# Etch_a_Sketch_Front.net
KiCad netlist of a schematic drawn in EAGLE
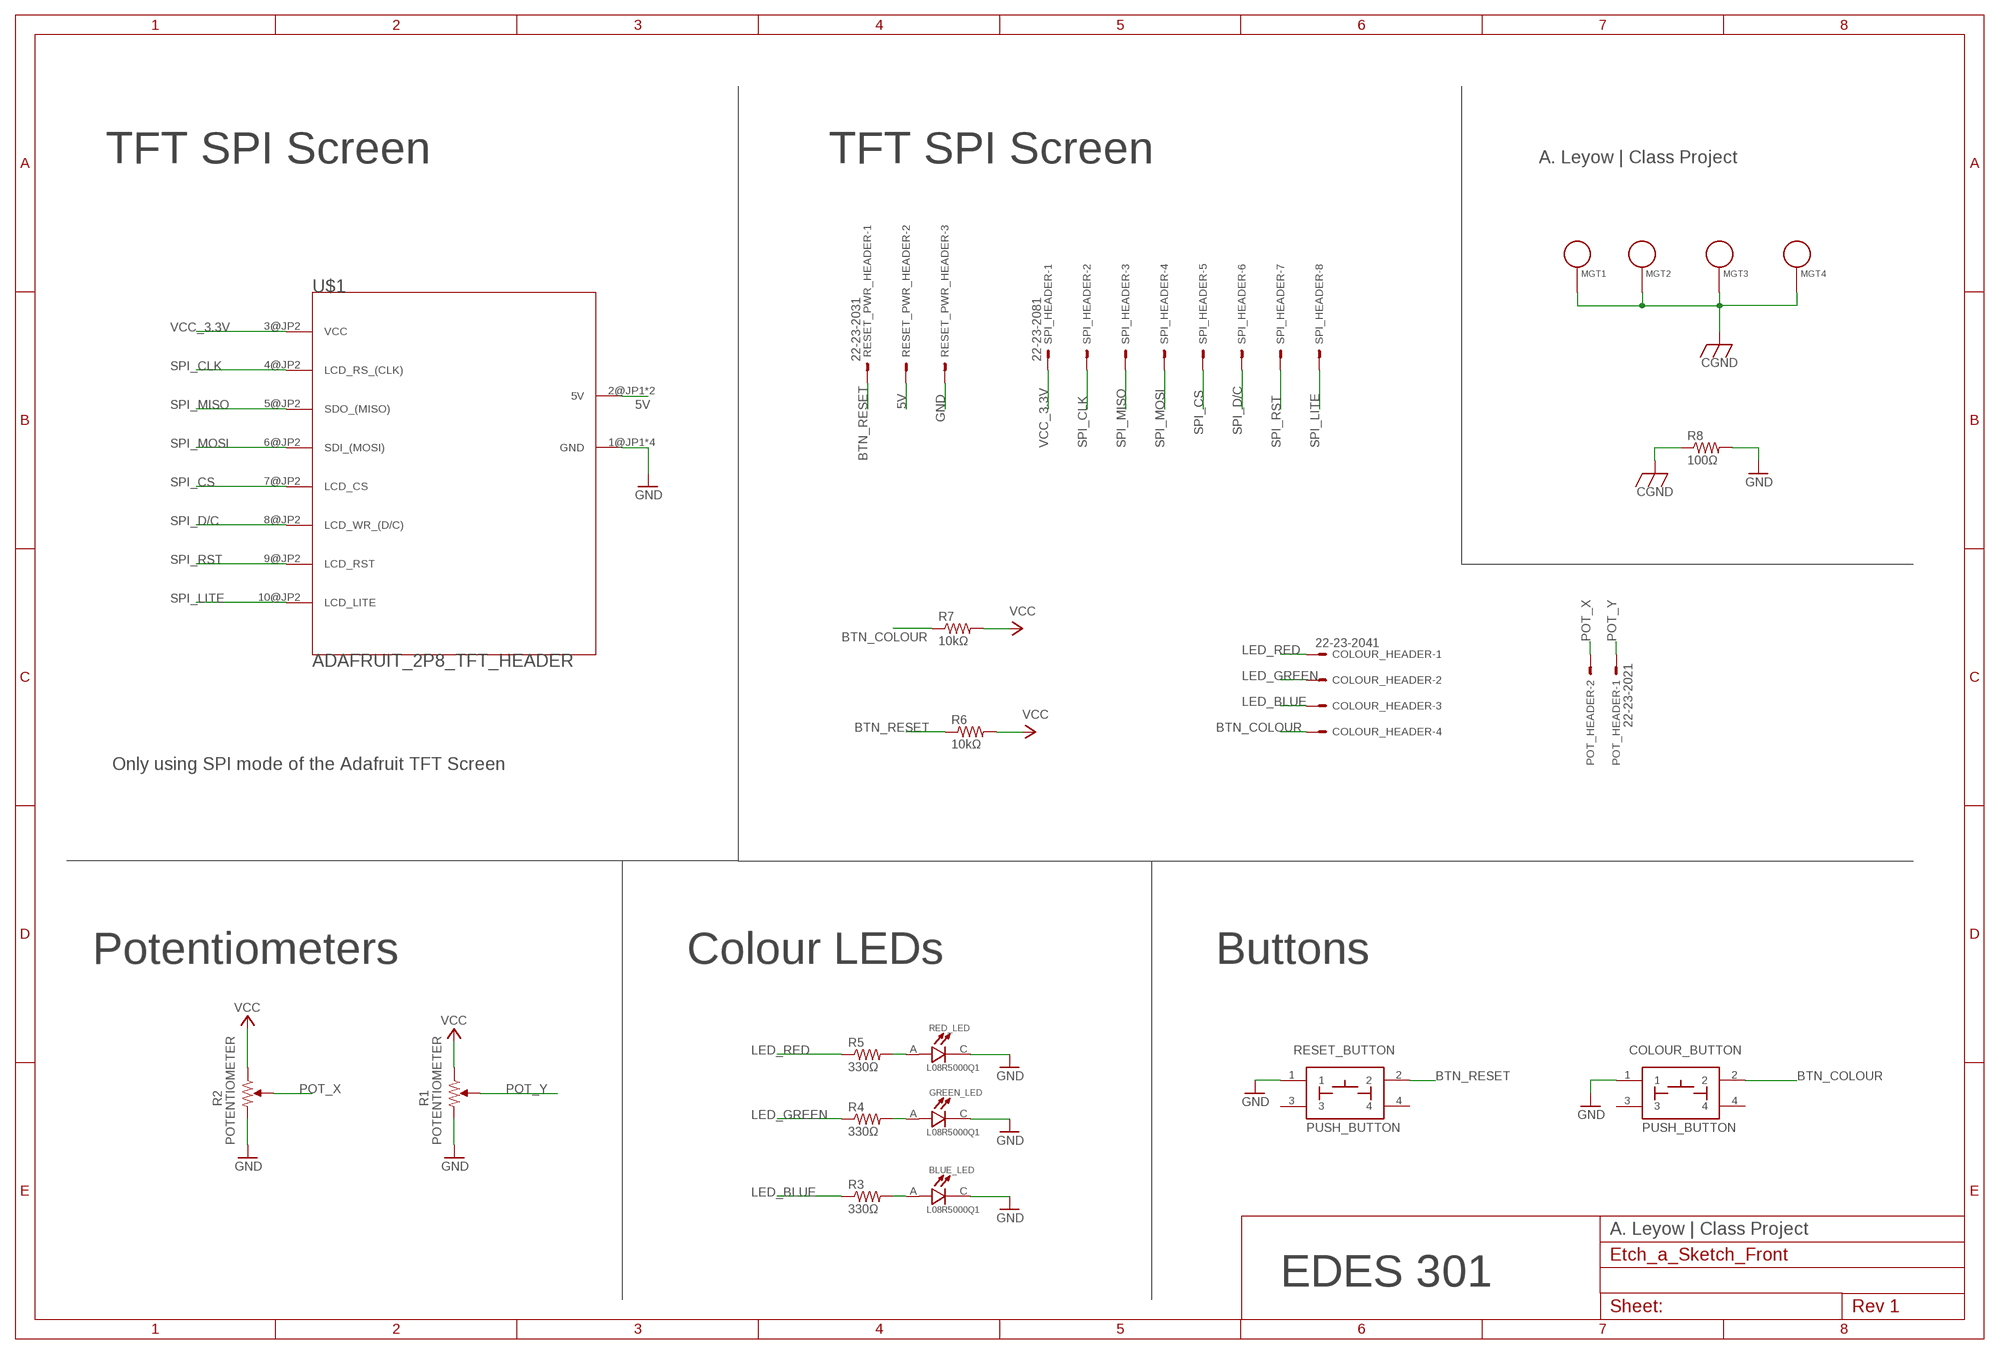
[diagram p0: schematic, sheet 1]

(export (version "E")
  (design (tool "Eeschema 10.0.6"))
  (components
    (comp (ref "BLUE_LED")
      (value "L08R5000Q1")
      (footprint "eagle-import:LEDRD254W57D500H1070")
      (fields (field (name "MF") "LED Technology"))
      (libsource (lib "eagle-import") (part "L08R5000Q1"))
    )
    (comp (ref "COLOUR_BUTTON")
      (value "PUSH_BUTTON")
      (footprint "eagle-import:BUTTON_12.5MM")
      (libsource (lib "eagle-import") (part "PUSH_BUTTON"))
    )
    (comp (ref "COLOUR_HEADER")
      (value "22-23-2041")
      (footprint "eagle-import:22-23-2041")
      (fields (field (name "MF") "MOLEX"))
      (libsource (lib "eagle-import") (part "22-23-2041"))
    )
    (comp (ref "GREEN_LED")
      (value "L08R5000Q1")
      (footprint "eagle-import:LEDRD254W57D500H1070")
      (fields (field (name "MF") "LED Technology"))
      (libsource (lib "eagle-import") (part "L08R5000Q1"))
    )
    (comp (ref "MGT1")
      (value "MOUNTING_HOLE")
      (footprint "eagle-import:MOUNTING_HOLE")
      (libsource (lib "eagle-import") (part "MOUNTING_HOLE"))
    )
    (comp (ref "MGT2")
      (value "MOUNTING_HOLE")
      (footprint "eagle-import:MOUNTING_HOLE")
      (libsource (lib "eagle-import") (part "MOUNTING_HOLE"))
    )
    (comp (ref "MGT3")
      (value "MOUNTING_HOLE")
      (footprint "eagle-import:MOUNTING_HOLE")
      (libsource (lib "eagle-import") (part "MOUNTING_HOLE"))
    )
    (comp (ref "MGT4")
      (value "MOUNTING_HOLE")
      (footprint "eagle-import:MOUNTING_HOLE")
      (libsource (lib "eagle-import") (part "MOUNTING_HOLE"))
    )
    (comp (ref "POT_HEADER")
      (value "22-23-2021")
      (footprint "eagle-import:22-23-2021")
      (fields (field (name "MF") "MOLEX"))
      (libsource (lib "eagle-import") (part "22-23-2021"))
    )
    (comp (ref "R1")
      (value "POTENTIOMETER")
      (footprint "eagle-import:POT-PO90S")
      (libsource (lib "eagle-import") (part "POTENTIOMETER"))
    )
    (comp (ref "R2")
      (value "POTENTIOMETER")
      (footprint "eagle-import:POT-PO90S")
      (libsource (lib "eagle-import") (part "POTENTIOMETER"))
    )
    (comp (ref "R3")
      (value "330Ω")
      (footprint "eagle-import:R0805")
      (libsource (lib "eagle-import") (part "R-US_R0805"))
    )
    (comp (ref "R4")
      (value "330Ω")
      (footprint "eagle-import:R0805")
      (libsource (lib "eagle-import") (part "R-US_R0805"))
    )
    (comp (ref "R5")
      (value "330Ω")
      (footprint "eagle-import:R0805")
      (libsource (lib "eagle-import") (part "R-US_R0805"))
    )
    (comp (ref "R6")
      (value "10kΩ")
      (footprint "eagle-import:R0805")
      (libsource (lib "eagle-import") (part "R-US_R0805"))
    )
    (comp (ref "R7")
      (value "10kΩ")
      (footprint "eagle-import:R0805")
      (libsource (lib "eagle-import") (part "R-US_R0805"))
    )
    (comp (ref "R8")
      (value "100Ω")
      (footprint "eagle-import:R0805")
      (libsource (lib "eagle-import") (part "R-US_R0805"))
    )
    (comp (ref "RED_LED")
      (value "L08R5000Q1")
      (footprint "eagle-import:LEDRD254W57D500H1070")
      (fields (field (name "MF") "LED Technology"))
      (libsource (lib "eagle-import") (part "L08R5000Q1"))
    )
    (comp (ref "RESET_BUTTON")
      (value "PUSH_BUTTON")
      (footprint "eagle-import:BUTTON_12.5MM")
      (libsource (lib "eagle-import") (part "PUSH_BUTTON"))
    )
    (comp (ref "RESET_PWR_HEADER")
      (value "22-23-2031")
      (footprint "eagle-import:22-23-2031")
      (fields (field (name "MF") "MOLEX"))
      (libsource (lib "eagle-import") (part "22-23-2031"))
    )
    (comp (ref "SPI_HEADER")
      (value "22-23-2081")
      (footprint "eagle-import:22-23-2081")
      (fields (field (name "MF") "MOLEX"))
      (libsource (lib "eagle-import") (part "22-23-2081"))
    )
    (comp (ref "U$1")
      (value "ADAFRUIT_2P8_TFT_HEADER")
      (footprint "eagle-import:ADAFRUIT_2P8_TFT_HEADER")
      (libsource (lib "eagle-import") (part "ADAFRUIT_2P8_TFT_HEADER"))
    )
  )
  (nets
    (net (code "1") (name "/5V") (class "Default")
      (node (ref "RESET_PWR_HEADER") (pin "2") (pinfunction "S_2") (pintype "passive"))
      (node (ref "U$1") (pin "2@JP1") (pinfunction "5V_2@JP1") (pintype "power_in"))
      (node (ref "U$1") (pin "2@JP2") (pinfunction "5V_2@JP2") (pintype "power_in"))
    )
    (net (code "2") (name "/BTN_COLOUR") (class "Default")
      (node (ref "COLOUR_BUTTON") (pin "2") (pinfunction "2_2") (pintype "bidirectional"))
      (node (ref "COLOUR_HEADER") (pin "4") (pinfunction "S_4") (pintype "passive"))
      (node (ref "R7") (pin "1") (pinfunction "1_1") (pintype "passive"))
    )
    (net (code "3") (name "/BTN_RESET") (class "Default")
      (node (ref "R6") (pin "1") (pinfunction "1_1") (pintype "passive"))
      (node (ref "RESET_BUTTON") (pin "2") (pinfunction "2_2") (pintype "bidirectional"))
      (node (ref "RESET_PWR_HEADER") (pin "1") (pinfunction "S_1") (pintype "passive"))
    )
    (net (code "4") (name "/LED_BLUE") (class "Default")
      (node (ref "COLOUR_HEADER") (pin "3") (pinfunction "S_3") (pintype "passive"))
      (node (ref "R3") (pin "1") (pinfunction "1_1") (pintype "passive"))
    )
    (net (code "5") (name "/LED_GREEN") (class "Default")
      (node (ref "COLOUR_HEADER") (pin "2") (pinfunction "S_2") (pintype "passive"))
      (node (ref "R4") (pin "1") (pinfunction "1_1") (pintype "passive"))
    )
    (net (code "6") (name "/LED_RED") (class "Default")
      (node (ref "COLOUR_HEADER") (pin "1") (pinfunction "S_1") (pintype "passive"))
      (node (ref "R5") (pin "1") (pinfunction "1_1") (pintype "passive"))
    )
    (net (code "7") (name "/POT_X") (class "Default")
      (node (ref "POT_HEADER") (pin "2") (pinfunction "S_2") (pintype "passive"))
      (node (ref "R2") (pin "S") (pinfunction "S_S") (pintype "bidirectional"))
    )
    (net (code "8") (name "/POT_Y") (class "Default")
      (node (ref "POT_HEADER") (pin "1") (pinfunction "S_1") (pintype "passive"))
      (node (ref "R1") (pin "S") (pinfunction "S_S") (pintype "bidirectional"))
    )
    (net (code "9") (name "/SPI_CLK") (class "Default")
      (node (ref "SPI_HEADER") (pin "2") (pinfunction "S_2") (pintype "passive"))
      (node (ref "U$1") (pin "4@JP2") (pinfunction "LCD_RS_(CLK)_4@JP2") (pintype "input"))
    )
    (net (code "10") (name "/SPI_CS") (class "Default")
      (node (ref "SPI_HEADER") (pin "5") (pinfunction "S_5") (pintype "passive"))
      (node (ref "U$1") (pin "7@JP2") (pinfunction "LCD_CS_7@JP2") (pintype "input"))
    )
    (net (code "11") (name "/SPI_D{slash}C") (class "Default")
      (node (ref "SPI_HEADER") (pin "6") (pinfunction "S_6") (pintype "passive"))
      (node (ref "U$1") (pin "8@JP2") (pinfunction "LCD_WR_(D/C)_8@JP2") (pintype "input"))
    )
    (net (code "12") (name "/SPI_LITE") (class "Default")
      (node (ref "SPI_HEADER") (pin "8") (pinfunction "S_8") (pintype "passive"))
      (node (ref "U$1") (pin "10@JP2") (pinfunction "LCD_LITE_10@JP2") (pintype "input"))
    )
    (net (code "13") (name "/SPI_MISO") (class "Default")
      (node (ref "SPI_HEADER") (pin "3") (pinfunction "S_3") (pintype "passive"))
      (node (ref "U$1") (pin "5@JP2") (pinfunction "SDO_(MISO)_5@JP2") (pintype "output"))
    )
    (net (code "14") (name "/SPI_MOSI") (class "Default")
      (node (ref "SPI_HEADER") (pin "4") (pinfunction "S_4") (pintype "passive"))
      (node (ref "U$1") (pin "6@JP2") (pinfunction "SDI_(MOSI)_6@JP2") (pintype "input"))
    )
    (net (code "15") (name "/SPI_RST") (class "Default")
      (node (ref "SPI_HEADER") (pin "7") (pinfunction "S_7") (pintype "passive"))
      (node (ref "U$1") (pin "9@JP2") (pinfunction "LCD_RST_9@JP2") (pintype "input"))
    )
    (net (code "16") (name "/VCC_3.3V") (class "Default")
      (node (ref "SPI_HEADER") (pin "1") (pinfunction "S_1") (pintype "passive"))
      (node (ref "U$1") (pin "3@JP2") (pinfunction "VCC_3@JP2") (pintype "power_in"))
    )
    (net (code "17") (name "CGND") (class "Default")
      (node (ref "MGT1") (pin "P$1") (pinfunction "P$1_P$1") (pintype "bidirectional"))
      (node (ref "MGT2") (pin "P$1") (pinfunction "P$1_P$1") (pintype "bidirectional"))
      (node (ref "MGT3") (pin "P$1") (pinfunction "P$1_P$1") (pintype "bidirectional"))
      (node (ref "MGT4") (pin "P$1") (pinfunction "P$1_P$1") (pintype "bidirectional"))
      (node (ref "R8") (pin "1") (pinfunction "1_1") (pintype "passive"))
    )
    (net (code "18") (name "GND") (class "Default")
      (node (ref "BLUE_LED") (pin "C") (pinfunction "C_C") (pintype "passive"))
      (node (ref "COLOUR_BUTTON") (pin "1") (pinfunction "1_1") (pintype "bidirectional"))
      (node (ref "GREEN_LED") (pin "C") (pinfunction "C_C") (pintype "passive"))
      (node (ref "R1") (pin "CW") (pinfunction "CW_CW") (pintype "passive"))
      (node (ref "R2") (pin "CW") (pinfunction "CW_CW") (pintype "passive"))
      (node (ref "R8") (pin "2") (pinfunction "2_2") (pintype "passive"))
      (node (ref "RED_LED") (pin "C") (pinfunction "C_C") (pintype "passive"))
      (node (ref "RESET_BUTTON") (pin "1") (pinfunction "1_1") (pintype "bidirectional"))
      (node (ref "RESET_PWR_HEADER") (pin "3") (pinfunction "S_3") (pintype "passive"))
      (node (ref "U$1") (pin "11@JP2") (pinfunction "GND_11@JP2") (pintype "power_in"))
      (node (ref "U$1") (pin "12@JP1") (pinfunction "GND_12@JP1") (pintype "power_in"))
      (node (ref "U$1") (pin "1@JP1") (pinfunction "GND_1@JP1") (pintype "power_in"))
      (node (ref "U$1") (pin "1@JP2") (pinfunction "GND_1@JP2") (pintype "power_in"))
    )
    (net (code "19") (name "Net-(BLUE_LED-PadA)") (class "Default")
      (node (ref "BLUE_LED") (pin "A") (pinfunction "A_A") (pintype "passive"))
      (node (ref "R3") (pin "2") (pinfunction "2_2") (pintype "passive"))
    )
    (net (code "20") (name "Net-(GREEN_LED-PadA)") (class "Default")
      (node (ref "GREEN_LED") (pin "A") (pinfunction "A_A") (pintype "passive"))
      (node (ref "R4") (pin "2") (pinfunction "2_2") (pintype "passive"))
    )
    (net (code "21") (name "Net-(R5-Pad2)") (class "Default")
      (node (ref "R5") (pin "2") (pinfunction "2_2") (pintype "passive"))
      (node (ref "RED_LED") (pin "A") (pinfunction "A_A") (pintype "passive"))
    )
    (net (code "22") (name "VCC") (class "Default")
      (node (ref "R1") (pin "CCW") (pinfunction "CCW_CCW") (pintype "passive"))
      (node (ref "R2") (pin "CCW") (pinfunction "CCW_CCW") (pintype "passive"))
      (node (ref "R6") (pin "2") (pinfunction "2_2") (pintype "passive"))
      (node (ref "R7") (pin "2") (pinfunction "2_2") (pintype "passive"))
    )
    (net (code "23") (name "unconnected-(COLOUR_BUTTON-Pad3)") (class "Default")
      (node (ref "COLOUR_BUTTON") (pin "3") (pinfunction "3_3") (pintype "bidirectional"))
    )
    (net (code "24") (name "unconnected-(COLOUR_BUTTON-Pad4)") (class "Default")
      (node (ref "COLOUR_BUTTON") (pin "4") (pinfunction "4_4") (pintype "bidirectional"))
    )
    (net (code "25") (name "unconnected-(RESET_BUTTON-Pad3)") (class "Default")
      (node (ref "RESET_BUTTON") (pin "3") (pinfunction "3_3") (pintype "bidirectional"))
    )
    (net (code "26") (name "unconnected-(RESET_BUTTON-Pad4)") (class "Default")
      (node (ref "RESET_BUTTON") (pin "4") (pinfunction "4_4") (pintype "bidirectional"))
    )
  )
)
